# Controller_Headers.net
KiCad netlist of a schematic drawn in Altium Designer
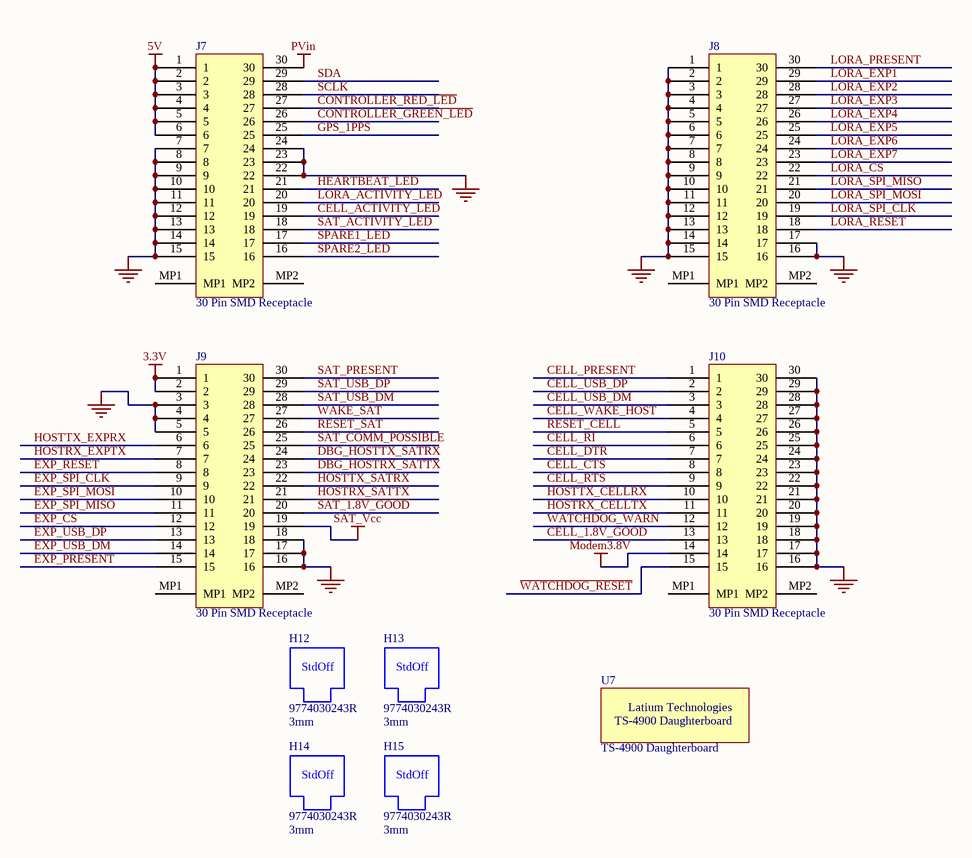
[diagram p0: Controller Headers.SchDoc]

(export (version "E")
  (design (tool "Eeschema 10.0.6"))
  (components
    (comp (ref "H12")
      (value "9774030243R")
      (footprint "Wurth 9774030243R")
      (description "ROUND STANDOFF M2X0.4 STEEL 3MM")
      (fields (field (name "MANUFACTURER") "Wurth Electronics Inc") (field (name "HEIGHT") "3mm"))
      (libsource (lib "Latium Component Library") (part "SMD M3 Spacer"))
    )
    (comp (ref "H13")
      (value "9774030243R")
      (footprint "Wurth 9774030243R")
      (description "ROUND STANDOFF M2X0.4 STEEL 3MM")
      (fields (field (name "MANUFACTURER") "Wurth Electronics Inc") (field (name "HEIGHT") "3mm"))
      (libsource (lib "Latium Component Library") (part "SMD M3 Spacer"))
    )
    (comp (ref "H14")
      (value "9774030243R")
      (footprint "Wurth 9774030243R")
      (description "ROUND STANDOFF M2X0.4 STEEL 3MM")
      (fields (field (name "MANUFACTURER") "Wurth Electronics Inc") (field (name "HEIGHT") "3mm"))
      (libsource (lib "Latium Component Library") (part "SMD M3 Spacer"))
    )
    (comp (ref "H15")
      (value "9774030243R")
      (footprint "Wurth 9774030243R")
      (description "ROUND STANDOFF M2X0.4 STEEL 3MM")
      (fields (field (name "MANUFACTURER") "Wurth Electronics Inc") (field (name "HEIGHT") "3mm"))
      (libsource (lib "Latium Component Library") (part "SMD M3 Spacer"))
    )
    (comp (ref "J7")
      (value "30 Pin SMD Receptacle")
      (footprint "10132798-031100LF")
      (description "CONN RCPT 30POS SMD GOLD")
      (fields
        (field (name "MANUFACTURER") "Amphenol ICC (FCI)")
        (field (name "MANUFACTURER PART NUMBER") "10132798-031100LF")
      )
      (libsource (lib "Latium Component Library") (part "Amphenol 30 Pos BergStak Plug"))
    )
    (comp (ref "J8")
      (value "30 Pin SMD Receptacle")
      (footprint "10132798-031100LF")
      (description "CONN RCPT 30POS SMD GOLD")
      (fields
        (field (name "MANUFACTURER") "Amphenol ICC (FCI)")
        (field (name "MANUFACTURER PART NUMBER") "10132798-031100LF")
      )
      (libsource (lib "Latium Component Library") (part "Amphenol 30 Pos BergStak Plug"))
    )
    (comp (ref "J9")
      (value "30 Pin SMD Receptacle")
      (footprint "10132798-031100LF")
      (description "CONN RCPT 30POS SMD GOLD")
      (fields
        (field (name "MANUFACTURER") "Amphenol ICC (FCI)")
        (field (name "MANUFACTURER PART NUMBER") "10132798-031100LF")
      )
      (libsource (lib "Latium Component Library") (part "Amphenol 30 Pos BergStak Plug"))
    )
    (comp (ref "J10")
      (value "30 Pin SMD Receptacle")
      (footprint "10132798-031100LF")
      (description "CONN RCPT 30POS SMD GOLD")
      (fields
        (field (name "MANUFACTURER") "Amphenol ICC (FCI)")
        (field (name "MANUFACTURER PART NUMBER") "10132798-031100LF")
      )
      (libsource (lib "Latium Component Library") (part "Amphenol 30 Pos BergStak Plug"))
    )
    (comp (ref "U7")
      (value "TS-4900 Daughterboard")
      (footprint "TS-4900 Daughterboard")
      (libsource (lib "Latium Component Library") (part "TS-4900 Daughterboard"))
    )
  )
  (nets
    (net (code "1") (name "/CELL_ACTIVITY_LED") (class "Default")
      (node (ref "J7") (pin "19") (pinfunction "19_19") (pintype "passive"))
    )
    (net (code "2") (name "/CELL_CTS") (class "Default")
      (node (ref "J10") (pin "8") (pinfunction "8_8") (pintype "passive"))
    )
    (net (code "3") (name "/CELL_DTR") (class "Default")
      (node (ref "J10") (pin "7") (pinfunction "7_7") (pintype "passive"))
    )
    (net (code "4") (name "/CELL_PRESENT") (class "Default")
      (node (ref "J10") (pin "1") (pinfunction "1_1") (pintype "passive"))
    )
    (net (code "5") (name "/CELL_RI") (class "Default")
      (node (ref "J10") (pin "6") (pinfunction "6_6") (pintype "passive"))
    )
    (net (code "6") (name "/CELL_RTS") (class "Default")
      (node (ref "J10") (pin "9") (pinfunction "9_9") (pintype "passive"))
    )
    (net (code "7") (name "/CELL_USB_DM") (class "Default")
      (node (ref "J10") (pin "3") (pinfunction "3_3") (pintype "passive"))
    )
    (net (code "8") (name "/CELL_USB_DP") (class "Default")
      (node (ref "J10") (pin "2") (pinfunction "2_2") (pintype "passive"))
    )
    (net (code "9") (name "/DBG_HOSTRX_SATTX") (class "Default")
      (node (ref "J9") (pin "23") (pinfunction "23_23") (pintype "passive"))
    )
    (net (code "10") (name "/DBG_HOSTTX_SATRX") (class "Default")
      (node (ref "J9") (pin "24") (pinfunction "24_24") (pintype "passive"))
    )
    (net (code "11") (name "/EXP_PRESENT") (class "Default")
      (node (ref "J9") (pin "15") (pinfunction "15_15") (pintype "passive"))
    )
    (net (code "12") (name "/EXP_RESET") (class "Default")
      (node (ref "J9") (pin "8") (pinfunction "8_8") (pintype "passive"))
    )
    (net (code "13") (name "/EXP_SPI_CLK") (class "Default")
      (node (ref "J9") (pin "9") (pinfunction "9_9") (pintype "passive"))
    )
    (net (code "14") (name "/EXP_SPI_MISO") (class "Default")
      (node (ref "J9") (pin "11") (pinfunction "11_11") (pintype "passive"))
    )
    (net (code "15") (name "/EXP_SPI_MOSI") (class "Default")
      (node (ref "J9") (pin "10") (pinfunction "10_10") (pintype "passive"))
    )
    (net (code "16") (name "/EXP_USB_DM") (class "Default")
      (node (ref "J9") (pin "14") (pinfunction "14_14") (pintype "passive"))
    )
    (net (code "17") (name "/EXP_USB_DP") (class "Default")
      (node (ref "J9") (pin "13") (pinfunction "13_13") (pintype "passive"))
    )
    (net (code "18") (name "/GPS_1PPS") (class "Default")
      (node (ref "J7") (pin "25") (pinfunction "25_25") (pintype "passive"))
    )
    (net (code "19") (name "/HEARTBEAT_LED") (class "Default")
      (node (ref "J7") (pin "21") (pinfunction "21_21") (pintype "passive"))
    )
    (net (code "20") (name "/HOSTRX_CELLTX") (class "Default")
      (node (ref "J10") (pin "11") (pinfunction "11_11") (pintype "passive"))
    )
    (net (code "21") (name "/HOSTRX_EXPTX") (class "Default")
      (node (ref "J9") (pin "7") (pinfunction "7_7") (pintype "passive"))
    )
    (net (code "22") (name "/HOSTRX_SATTX") (class "Default")
      (node (ref "J9") (pin "21") (pinfunction "21_21") (pintype "passive"))
    )
    (net (code "23") (name "/HOSTTX_CELLRX") (class "Default")
      (node (ref "J10") (pin "10") (pinfunction "10_10") (pintype "passive"))
    )
    (net (code "24") (name "/HOSTTX_EXPRX") (class "Default")
      (node (ref "J9") (pin "6") (pinfunction "6_6") (pintype "passive"))
    )
    (net (code "25") (name "/HOSTTX_SATRX") (class "Default")
      (node (ref "J9") (pin "22") (pinfunction "22_22") (pintype "passive"))
    )
    (net (code "26") (name "/LORA_ACTIVITY_LED") (class "Default")
      (node (ref "J7") (pin "20") (pinfunction "20_20") (pintype "passive"))
    )
    (net (code "27") (name "/LORA_EXP1") (class "Default")
      (node (ref "J8") (pin "29") (pinfunction "29_29") (pintype "passive"))
    )
    (net (code "28") (name "/LORA_EXP2") (class "Default")
      (node (ref "J8") (pin "28") (pinfunction "28_28") (pintype "passive"))
    )
    (net (code "29") (name "/LORA_EXP3") (class "Default")
      (node (ref "J8") (pin "27") (pinfunction "27_27") (pintype "passive"))
    )
    (net (code "30") (name "/LORA_EXP4") (class "Default")
      (node (ref "J8") (pin "26") (pinfunction "26_26") (pintype "passive"))
    )
    (net (code "31") (name "/LORA_EXP5") (class "Default")
      (node (ref "J8") (pin "25") (pinfunction "25_25") (pintype "passive"))
    )
    (net (code "32") (name "/LORA_EXP6") (class "Default")
      (node (ref "J8") (pin "24") (pinfunction "24_24") (pintype "passive"))
    )
    (net (code "33") (name "/LORA_EXP7") (class "Default")
      (node (ref "J8") (pin "23") (pinfunction "23_23") (pintype "passive"))
    )
    (net (code "34") (name "/LORA_PRESENT") (class "Default")
      (node (ref "J8") (pin "30") (pinfunction "30_30") (pintype "passive"))
    )
    (net (code "35") (name "/LORA_RESET") (class "Default")
      (node (ref "J8") (pin "18") (pinfunction "18_18") (pintype "passive"))
    )
    (net (code "36") (name "/LORA_SPI_CLK") (class "Default")
      (node (ref "J8") (pin "19") (pinfunction "19_19") (pintype "passive"))
    )
    (net (code "37") (name "/LORA_SPI_MISO") (class "Default")
      (node (ref "J8") (pin "21") (pinfunction "21_21") (pintype "passive"))
    )
    (net (code "38") (name "/LORA_SPI_MOSI") (class "Default")
      (node (ref "J8") (pin "20") (pinfunction "20_20") (pintype "passive"))
    )
    (net (code "39") (name "/RESET_CELL") (class "Default")
      (node (ref "J10") (pin "5") (pinfunction "5_5") (pintype "passive"))
    )
    (net (code "40") (name "/RESET_SAT") (class "Default")
      (node (ref "J9") (pin "26") (pinfunction "26_26") (pintype "passive"))
    )
    (net (code "41") (name "/SAT_ACTIVITY_LED") (class "Default")
      (node (ref "J7") (pin "18") (pinfunction "18_18") (pintype "passive"))
    )
    (net (code "42") (name "/SAT_COMM_POSSIBLE") (class "Default")
      (node (ref "J9") (pin "25") (pinfunction "25_25") (pintype "passive"))
    )
    (net (code "43") (name "/SAT_PRESENT") (class "Default")
      (node (ref "J9") (pin "30") (pinfunction "30_30") (pintype "passive"))
    )
    (net (code "44") (name "/SAT_USB_DM") (class "Default")
      (node (ref "J9") (pin "28") (pinfunction "28_28") (pintype "passive"))
    )
    (net (code "45") (name "/SAT_USB_DP") (class "Default")
      (node (ref "J9") (pin "29") (pinfunction "29_29") (pintype "passive"))
    )
    (net (code "46") (name "/SCLK") (class "Default")
      (node (ref "J7") (pin "28") (pinfunction "28_28") (pintype "passive"))
    )
    (net (code "47") (name "/SDA") (class "Default")
      (node (ref "J7") (pin "29") (pinfunction "29_29") (pintype "passive"))
    )
    (net (code "48") (name "/SPARE1_LED") (class "Default")
      (node (ref "J7") (pin "17") (pinfunction "17_17") (pintype "passive"))
    )
    (net (code "49") (name "/SPARE2_LED") (class "Default")
      (node (ref "J7") (pin "16") (pinfunction "16_16") (pintype "passive"))
    )
    (net (code "50") (name "/WAKE_SAT") (class "Default")
      (node (ref "J9") (pin "27") (pinfunction "27_27") (pintype "passive"))
    )
    (net (code "51") (name "/WATCHDOG_WARN") (class "Default")
      (node (ref "J10") (pin "12") (pinfunction "12_12") (pintype "passive"))
    )
    (net (code "52") (name "/~{CELL_1.8V_GOOD}") (class "Default")
      (node (ref "J10") (pin "13") (pinfunction "13_13") (pintype "passive"))
    )
    (net (code "53") (name "/~{CELL_WAKE_HOST}") (class "Default")
      (node (ref "J10") (pin "4") (pinfunction "4_4") (pintype "passive"))
    )
    (net (code "54") (name "/~{CONTROLLER_GREEN_LED}") (class "Default")
      (node (ref "J7") (pin "26") (pinfunction "26_26") (pintype "passive"))
    )
    (net (code "55") (name "/~{CONTROLLER_RED_LED}") (class "Default")
      (node (ref "J7") (pin "27") (pinfunction "27_27") (pintype "passive"))
    )
    (net (code "56") (name "/~{EXP_CS}") (class "Default")
      (node (ref "J9") (pin "12") (pinfunction "12_12") (pintype "passive"))
    )
    (net (code "57") (name "/~{LORA_CS}") (class "Default")
      (node (ref "J8") (pin "22") (pinfunction "22_22") (pintype "passive"))
    )
    (net (code "58") (name "/~{SAT_1.8V_GOOD}") (class "Default")
      (node (ref "J9") (pin "20") (pinfunction "20_20") (pintype "passive"))
    )
    (net (code "59") (name "/~{WATCHDOG_RESET}") (class "Default")
      (node (ref "J10") (pin "15") (pinfunction "15_15") (pintype "passive"))
    )
    (net (code "60") (name "3.3V") (class "Default")
      (node (ref "J9") (pin "1") (pinfunction "1_1") (pintype "passive"))
      (node (ref "J9") (pin "2") (pinfunction "2_2") (pintype "passive"))
    )
    (net (code "61") (name "5V") (class "Default")
      (node (ref "J7") (pin "1") (pinfunction "1_1") (pintype "passive"))
      (node (ref "J7") (pin "2") (pinfunction "2_2") (pintype "passive"))
      (node (ref "J7") (pin "3") (pinfunction "3_3") (pintype "passive"))
      (node (ref "J7") (pin "4") (pinfunction "4_4") (pintype "passive"))
      (node (ref "J7") (pin "5") (pinfunction "5_5") (pintype "passive"))
      (node (ref "J7") (pin "6") (pinfunction "6_6") (pintype "passive"))
    )
    (net (code "62") (name "GND") (class "Default")
      (node (ref "J10") (pin "16") (pinfunction "16_16") (pintype "passive"))
      (node (ref "J10") (pin "17") (pinfunction "17_17") (pintype "passive"))
      (node (ref "J10") (pin "18") (pinfunction "18_18") (pintype "passive"))
      (node (ref "J10") (pin "19") (pinfunction "19_19") (pintype "passive"))
      (node (ref "J10") (pin "20") (pinfunction "20_20") (pintype "passive"))
      (node (ref "J10") (pin "21") (pinfunction "21_21") (pintype "passive"))
      (node (ref "J10") (pin "22") (pinfunction "22_22") (pintype "passive"))
      (node (ref "J10") (pin "23") (pinfunction "23_23") (pintype "passive"))
      (node (ref "J10") (pin "24") (pinfunction "24_24") (pintype "passive"))
      (node (ref "J10") (pin "25") (pinfunction "25_25") (pintype "passive"))
      (node (ref "J10") (pin "26") (pinfunction "26_26") (pintype "passive"))
      (node (ref "J10") (pin "27") (pinfunction "27_27") (pintype "passive"))
      (node (ref "J10") (pin "28") (pinfunction "28_28") (pintype "passive"))
      (node (ref "J10") (pin "29") (pinfunction "29_29") (pintype "passive"))
      (node (ref "J10") (pin "30") (pinfunction "30_30") (pintype "passive"))
      (node (ref "J7") (pin "10") (pinfunction "10_10") (pintype "passive"))
      (node (ref "J7") (pin "11") (pinfunction "11_11") (pintype "passive"))
      (node (ref "J7") (pin "12") (pinfunction "12_12") (pintype "passive"))
      (node (ref "J7") (pin "13") (pinfunction "13_13") (pintype "passive"))
      (node (ref "J7") (pin "14") (pinfunction "14_14") (pintype "passive"))
      (node (ref "J7") (pin "15") (pinfunction "15_15") (pintype "passive"))
      (node (ref "J7") (pin "22") (pinfunction "22_22") (pintype "passive"))
      (node (ref "J7") (pin "23") (pinfunction "23_23") (pintype "passive"))
      (node (ref "J7") (pin "24") (pinfunction "24_24") (pintype "passive"))
      (node (ref "J7") (pin "7") (pinfunction "7_7") (pintype "passive"))
      (node (ref "J7") (pin "8") (pinfunction "8_8") (pintype "passive"))
      (node (ref "J7") (pin "9") (pinfunction "9_9") (pintype "passive"))
      (node (ref "J8") (pin "1") (pinfunction "1_1") (pintype "passive"))
      (node (ref "J8") (pin "10") (pinfunction "10_10") (pintype "passive"))
      (node (ref "J8") (pin "11") (pinfunction "11_11") (pintype "passive"))
      (node (ref "J8") (pin "12") (pinfunction "12_12") (pintype "passive"))
      (node (ref "J8") (pin "13") (pinfunction "13_13") (pintype "passive"))
      (node (ref "J8") (pin "14") (pinfunction "14_14") (pintype "passive"))
      (node (ref "J8") (pin "15") (pinfunction "15_15") (pintype "passive"))
      (node (ref "J8") (pin "16") (pinfunction "16_16") (pintype "passive"))
      (node (ref "J8") (pin "17") (pinfunction "17_17") (pintype "passive"))
      (node (ref "J8") (pin "2") (pinfunction "2_2") (pintype "passive"))
      (node (ref "J8") (pin "3") (pinfunction "3_3") (pintype "passive"))
      (node (ref "J8") (pin "4") (pinfunction "4_4") (pintype "passive"))
      (node (ref "J8") (pin "5") (pinfunction "5_5") (pintype "passive"))
      (node (ref "J8") (pin "6") (pinfunction "6_6") (pintype "passive"))
      (node (ref "J8") (pin "7") (pinfunction "7_7") (pintype "passive"))
      (node (ref "J8") (pin "8") (pinfunction "8_8") (pintype "passive"))
      (node (ref "J8") (pin "9") (pinfunction "9_9") (pintype "passive"))
      (node (ref "J9") (pin "16") (pinfunction "16_16") (pintype "passive"))
      (node (ref "J9") (pin "17") (pinfunction "17_17") (pintype "passive"))
      (node (ref "J9") (pin "18") (pinfunction "18_18") (pintype "passive"))
      (node (ref "J9") (pin "3") (pinfunction "3_3") (pintype "passive"))
      (node (ref "J9") (pin "4") (pinfunction "4_4") (pintype "passive"))
      (node (ref "J9") (pin "5") (pinfunction "5_5") (pintype "passive"))
    )
    (net (code "63") (name "Modem3.8V") (class "Default")
      (node (ref "J10") (pin "14") (pinfunction "14_14") (pintype "passive"))
    )
    (net (code "64") (name "PVin") (class "Default")
      (node (ref "J7") (pin "30") (pinfunction "30_30") (pintype "passive"))
    )
    (net (code "65") (name "SAT_Vcc") (class "Default")
      (node (ref "J9") (pin "19") (pinfunction "19_19") (pintype "passive"))
    )
    (net (code "66") (name "unconnected-(J7-PadMP1)") (class "Default")
      (node (ref "J7") (pin "MP1") (pinfunction "MP1_MP1") (pintype "passive"))
    )
    (net (code "67") (name "unconnected-(J7-PadMP2)") (class "Default")
      (node (ref "J7") (pin "MP2") (pinfunction "MP2_MP2") (pintype "passive"))
    )
    (net (code "68") (name "unconnected-(J8-PadMP1)") (class "Default")
      (node (ref "J8") (pin "MP1") (pinfunction "MP1_MP1") (pintype "passive"))
    )
    (net (code "69") (name "unconnected-(J8-PadMP2)") (class "Default")
      (node (ref "J8") (pin "MP2") (pinfunction "MP2_MP2") (pintype "passive"))
    )
    (net (code "70") (name "unconnected-(J9-PadMP1)") (class "Default")
      (node (ref "J9") (pin "MP1") (pinfunction "MP1_MP1") (pintype "passive"))
    )
    (net (code "71") (name "unconnected-(J9-PadMP2)") (class "Default")
      (node (ref "J9") (pin "MP2") (pinfunction "MP2_MP2") (pintype "passive"))
    )
    (net (code "72") (name "unconnected-(J10-PadMP1)") (class "Default")
      (node (ref "J10") (pin "MP1") (pinfunction "MP1_MP1") (pintype "passive"))
    )
    (net (code "73") (name "unconnected-(J10-PadMP2)") (class "Default")
      (node (ref "J10") (pin "MP2") (pinfunction "MP2_MP2") (pintype "passive"))
    )
  )
)
